# Power-Sheet.net
KiCad netlist of a schematic drawn in Altium Designer
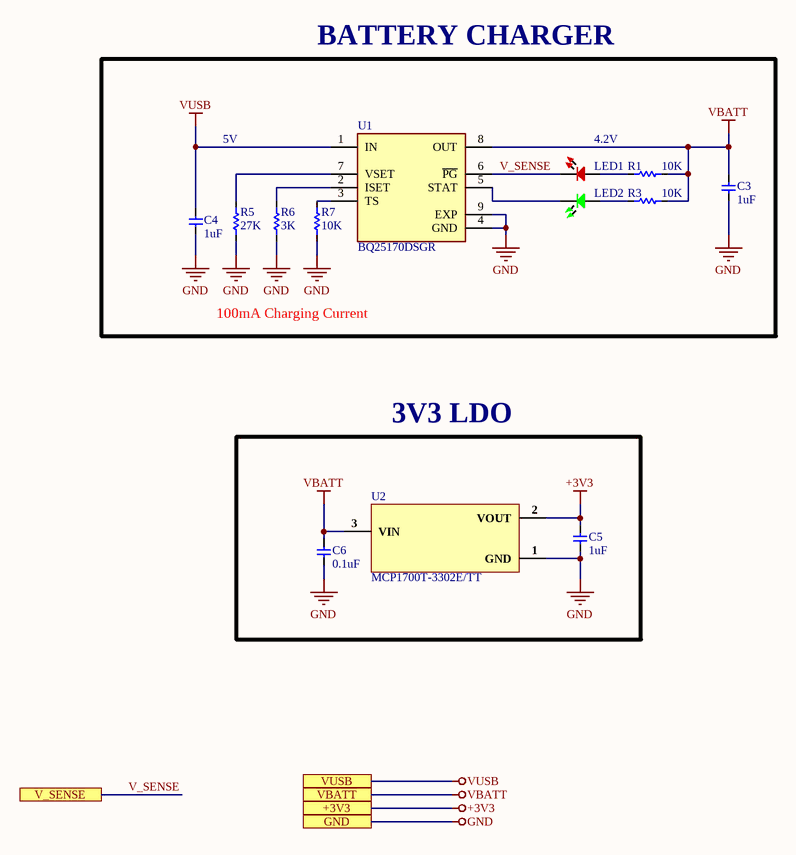
[diagram p0: Power-Sheet.SchDoc]

(export (version "E")
  (design (tool "Eeschema 10.0.6"))
  (components
    (comp (ref "C3")
      (value "1uF")
      (footprint "Cap-0402")
      (description "1 µF ±20% 6.3V Ceramic Capacitor X5R 0201 (0603 Metric)")
      (fields
        (field (name "MANUFACTURER") "Murata Electronics")
        (field (name "MANUFACTURER PART NUMBER") "GRM033R60J105MEA2D")
      )
      (libsource (lib "LED-Driver-Library") (part "GRM033R60J105MEA2D"))
    )
    (comp (ref "C4")
      (value "1uF")
      (footprint "Cap-0402")
      (description "1 µF ±20% 6.3V Ceramic Capacitor X5R 0201 (0603 Metric)")
      (fields
        (field (name "MANUFACTURER") "Murata Electronics")
        (field (name "MANUFACTURER PART NUMBER") "GRM033R60J105MEA2D")
      )
      (libsource (lib "LED-Driver-Library") (part "GRM033R60J105MEA2D"))
    )
    (comp (ref "C5")
      (value "1uF")
      (footprint "Cap-0402")
      (description "1 µF ±20% 6.3V Ceramic Capacitor X5R 0201 (0603 Metric)")
      (fields
        (field (name "MANUFACTURER") "Murata Electronics")
        (field (name "MANUFACTURER PART NUMBER") "GRM033R60J105MEA2D")
      )
      (libsource (lib "LED-Driver-Library") (part "GRM033R60J105MEA2D"))
    )
    (comp (ref "C6")
      (value "0.1uF")
      (footprint "Cap-0402")
      (description "0.1 µF ±10% 16V Ceramic Capacitor X7R 0402 (1005 Metric)")
      (fields
        (field (name "MANUFACTURER") "Murata Electronics")
        (field (name "MANUFACTURER PART NUMBER") "GRM155R71C104KA88J")
      )
      (libsource (lib "LED-Driver-Library") (part "GRM155R71C104KA88J"))
    )
    (comp (ref "LED1")
      (value "RED")
      (footprint "LED-0603")
      (description "RED LED 0603 Light Emitting Diodes")
      (fields
        (field (name "MANUFACTURER") "Foshan NationStar Optoelectronics")
        (field (name "MANUFACTURER PART NUMBER") "NCD0603R3")
      )
      (libsource (lib "LED-Driver-Library") (part "NCD0603R3"))
    )
    (comp (ref "LED2")
      (value "Emerald")
      (footprint "LED-0603")
      (description "Emerald 0603 Light Emitting Diodes (LED) ROHS")
      (fields
        (field (name "MANUFACTURER") "Foshan NationStar Optoelectronics")
        (field (name "MANUFACTURER PART NUMBER") "NCD0603G2")
      )
      (libsource (lib "LED-Driver-Library") (part "NCD0603G2"))
    )
    (comp (ref "R1")
      (value "10K")
      (footprint "Res-0402")
      (description "10 kOhms ±1% 0.063W, 1/16W Chip Resistor 0402 (1005 Metric) Moisture Resistant Thick Film")
      (fields
        (field (name "MANUFACTURER") "YAGEO")
        (field (name "MANUFACTURER PART NUMBER") "RC0402FR-0710KL")
      )
      (libsource (lib "LED-Driver-Library") (part "RC0603FR-0710KL"))
    )
    (comp (ref "R3")
      (value "10K")
      (footprint "Res-0402")
      (description "10 kOhms ±1% 0.063W, 1/16W Chip Resistor 0402 (1005 Metric) Moisture Resistant Thick Film")
      (fields
        (field (name "MANUFACTURER") "YAGEO")
        (field (name "MANUFACTURER PART NUMBER") "RC0402FR-0710KL")
      )
      (libsource (lib "LED-Driver-Library") (part "RC0603FR-0710KL"))
    )
    (comp (ref "R5")
      (value "27K")
      (footprint "Res-0402")
      (description "27 kOhms ±1% 0.063W, 1/16W Chip Resistor 0402 (1005 Metric) Moisture Resistant Thick Film")
      (fields
        (field (name "MANUFACTURER") "YAGEO")
        (field (name "MANUFACTURER PART NUMBER") "RC0402FR-0727KL")
      )
      (libsource (lib "LED-Driver-Library") (part "RC0402FR-0727KL"))
    )
    (comp (ref "R6")
      (value "3K")
      (footprint "Res-0402")
      (description "3 kOhms ±1% 0.063W, 1/16W Chip Resistor 0402 (1005 Metric) Moisture Resistant Thick Film")
      (fields
        (field (name "MANUFACTURER") "YAGEO")
        (field (name "MANUFACTURER PART NUMBER") "RC0402FR-073KL")
      )
      (libsource (lib "LED-Driver-Library") (part "RC0402FR-073KL"))
    )
    (comp (ref "R7")
      (value "10K")
      (footprint "Res-0402")
      (description "10 kOhms ±1% 0.063W, 1/16W Chip Resistor 0402 (1005 Metric) Moisture Resistant Thick Film")
      (fields
        (field (name "MANUFACTURER") "YAGEO")
        (field (name "MANUFACTURER PART NUMBER") "RC0402FR-0710KL")
      )
      (libsource (lib "LED-Driver-Library") (part "RC0603FR-0710KL"))
    )
    (comp (ref "U1")
      (value "BQ25170DSGR")
      (footprint "BQ25170DSGR")
      (description "Charger IC Multi-Chemistry 8-WSON (2x2)")
      (fields
        (field (name "MANUFACTURER") "Texas Instruments")
        (field (name "DIGIKEY PART NUMBER") "296-BQ25170DSGRDKR-ND")
      )
      (libsource (lib "LED-Driver-Library") (part "BQ25170DSGR"))
    )
    (comp (ref "U2")
      (value "MCP1700T-3302E/TT")
      (footprint "SOT-23")
      (description "IC REG LDO 3.3V 0.25A SOT23-3")
      (fields
        (field (name "MANUFACTURER") "Microchip")
        (field (name "DIGIKEY PART NUMBER") "MCP1700T3302ETTDKR-ND")
      )
      (libsource (lib "LED-Driver-Library") (part "MCP1700T-3302E/TT"))
    )
  )
  (nets
    (net (code "1") (name "+3V3") (class "Default")
      (node (ref "C5") (pin "2") (pinfunction "2_2") (pintype "passive"))
      (node (ref "U2") (pin "2") (pinfunction "VOUT_2") (pintype "passive"))
    )
    (net (code "2") (name "/V_SENSE") (class "Default")
      (node (ref "LED1") (pin "2") (pinfunction "2_2") (pintype "passive"))
      (node (ref "U1") (pin "6") (pinfunction "~{PG}_6") (pintype "passive"))
    )
    (net (code "3") (name "GND") (class "Default")
      (node (ref "C3") (pin "1") (pinfunction "1_1") (pintype "passive"))
      (node (ref "C4") (pin "1") (pinfunction "1_1") (pintype "passive"))
      (node (ref "C5") (pin "1") (pinfunction "1_1") (pintype "passive"))
      (node (ref "C6") (pin "1") (pinfunction "1_1") (pintype "passive"))
      (node (ref "R5") (pin "1") (pinfunction "1_1") (pintype "passive"))
      (node (ref "R6") (pin "1") (pinfunction "1_1") (pintype "passive"))
      (node (ref "R7") (pin "1") (pinfunction "1_1") (pintype "passive"))
      (node (ref "U1") (pin "4") (pinfunction "GND_4") (pintype "passive"))
      (node (ref "U1") (pin "9") (pinfunction "EXP_9") (pintype "passive"))
      (node (ref "U2") (pin "1") (pinfunction "GND_1") (pintype "passive"))
    )
    (net (code "4") (name "Net-(LED1-Pad1)") (class "Default")
      (node (ref "LED1") (pin "1") (pinfunction "1_1") (pintype "passive"))
      (node (ref "R1") (pin "2") (pinfunction "2_2") (pintype "passive"))
    )
    (net (code "5") (name "Net-(LED2-Pad1)") (class "Default")
      (node (ref "LED2") (pin "1") (pinfunction "1_1") (pintype "passive"))
      (node (ref "R3") (pin "2") (pinfunction "2_2") (pintype "passive"))
    )
    (net (code "6") (name "Net-(U1-ISET)") (class "Default")
      (node (ref "R6") (pin "2") (pinfunction "2_2") (pintype "passive"))
      (node (ref "U1") (pin "2") (pinfunction "ISET_2") (pintype "passive"))
    )
    (net (code "7") (name "Net-(U1-STAT)") (class "Default")
      (node (ref "LED2") (pin "2") (pinfunction "2_2") (pintype "passive"))
      (node (ref "U1") (pin "5") (pinfunction "STAT_5") (pintype "passive"))
    )
    (net (code "8") (name "Net-(U1-TS)") (class "Default")
      (node (ref "R7") (pin "2") (pinfunction "2_2") (pintype "passive"))
      (node (ref "U1") (pin "3") (pinfunction "TS_3") (pintype "passive"))
    )
    (net (code "9") (name "Net-(U1-VSET)") (class "Default")
      (node (ref "R5") (pin "2") (pinfunction "2_2") (pintype "passive"))
      (node (ref "U1") (pin "7") (pinfunction "VSET_7") (pintype "passive"))
    )
    (net (code "10") (name "VBATT") (class "Default")
      (node (ref "C3") (pin "2") (pinfunction "2_2") (pintype "passive"))
      (node (ref "C6") (pin "2") (pinfunction "2_2") (pintype "passive"))
      (node (ref "R1") (pin "1") (pinfunction "1_1") (pintype "passive"))
      (node (ref "R3") (pin "1") (pinfunction "1_1") (pintype "passive"))
      (node (ref "U1") (pin "8") (pinfunction "OUT_8") (pintype "passive"))
      (node (ref "U2") (pin "3") (pinfunction "VIN_3") (pintype "passive"))
    )
    (net (code "11") (name "VUSB") (class "Default")
      (node (ref "C4") (pin "2") (pinfunction "2_2") (pintype "passive"))
      (node (ref "U1") (pin "1") (pinfunction "IN_1") (pintype "passive"))
    )
  )
)
